# fuseV0_1.net
KiCad netlist of a schematic drawn in Altium Designer
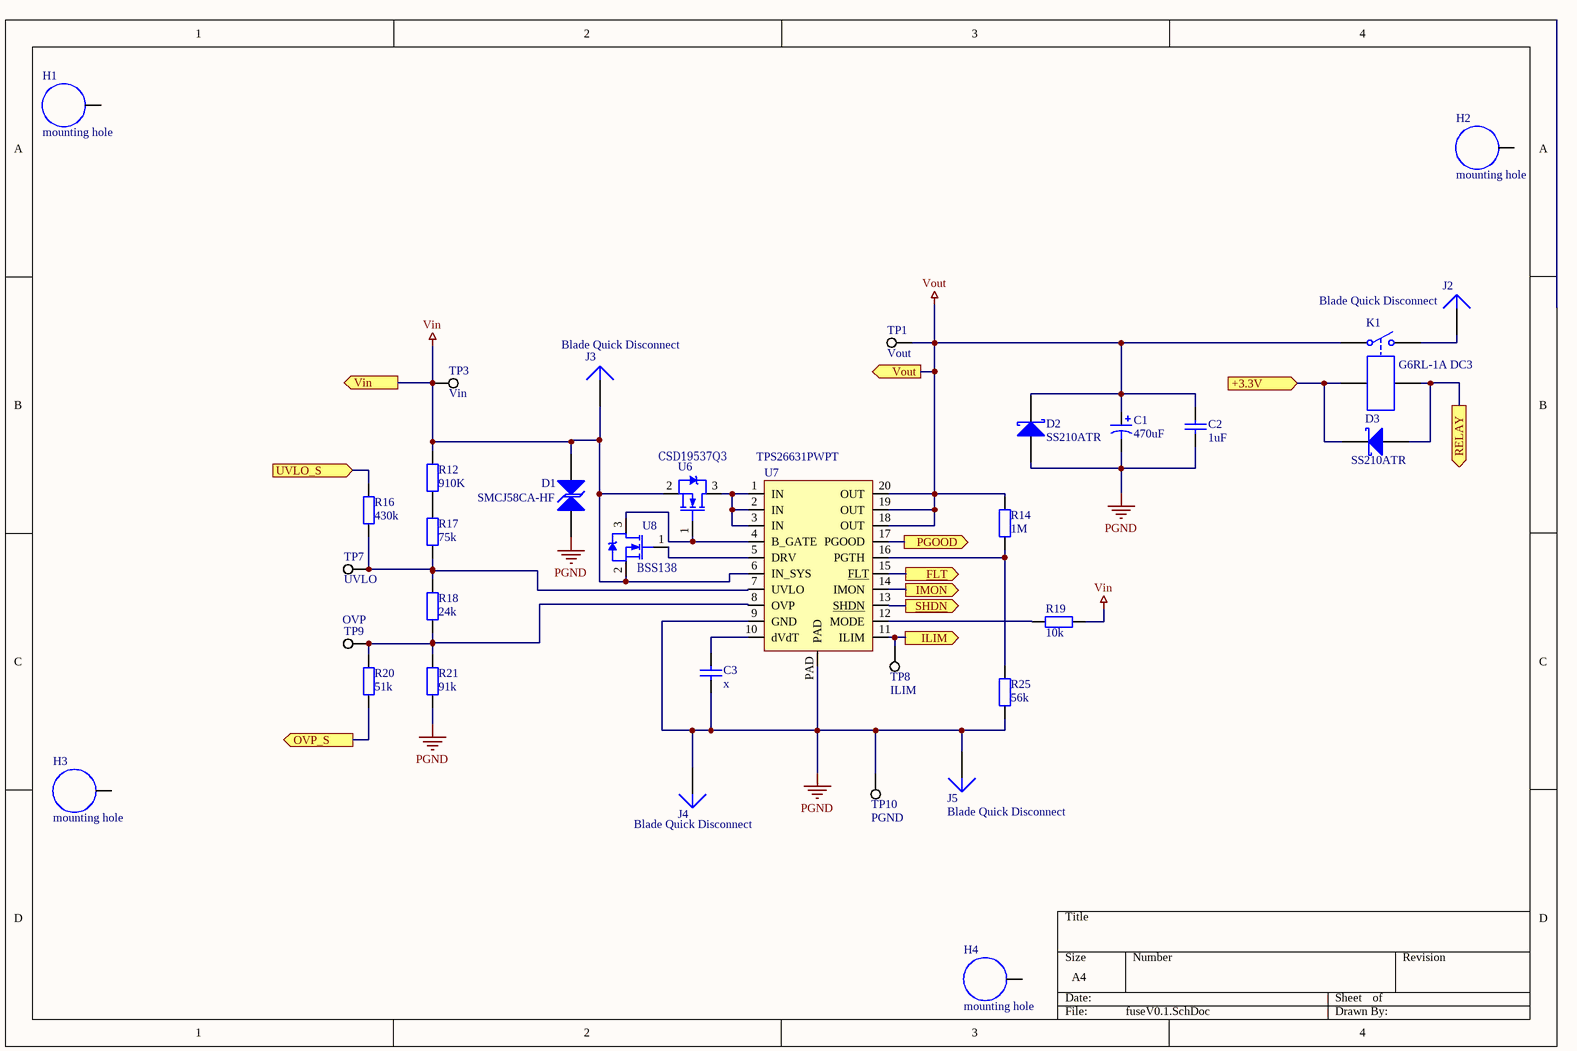
[diagram p0: fuseV0.1.SchDoc]

(export (version "E")
  (design (tool "Eeschema 10.0.6"))
  (components
    (comp (ref "C1")
      (value "470uF")
      (footprint "CAP_16MM_SMD")
      (libsource (lib "generic_components") (part "cap pol"))
    )
    (comp (ref "C2") (value "1uF") (footprint "0805") (libsource (lib "generic_components") (part "cap")))
    (comp (ref "C3") (value "x") (footprint "0805") (libsource (lib "generic_components") (part "cap")))
    (comp (ref "D1")
      (value "SMCJ58CA-HF")
      (footprint "DO-214AB-SMC Bipolar")
      (libsource (lib "generic_components") (part "TVS Diode"))
    )
    (comp (ref "D2")
      (value "SS210ATR")
      (footprint "DO-214AC, SMA")
      (libsource (lib "generic_components") (part "shotkey diode"))
    )
    (comp (ref "D3")
      (value "SS210ATR")
      (footprint "DO-214AC, SMA")
      (libsource (lib "generic_components") (part "shotkey diode"))
    )
    (comp (ref "H1")
      (value "mounting hole")
      (footprint "M3 HOLE iso")
      (libsource (lib "generic_components") (part "mounting hole"))
    )
    (comp (ref "H2")
      (value "mounting hole")
      (footprint "M3 HOLE iso")
      (libsource (lib "generic_components") (part "mounting hole"))
    )
    (comp (ref "H3")
      (value "mounting hole")
      (footprint "M3 HOLE iso")
      (libsource (lib "generic_components") (part "mounting hole"))
    )
    (comp (ref "H4")
      (value "mounting hole")
      (footprint "M3 HOLE iso")
      (libsource (lib "generic_components") (part "mounting hole"))
    )
    (comp (ref "J2")
      (value "Blade Quick Disconnect")
      (footprint "TE blade connector")
      (libsource (lib "generic_conn") (part "Blade Quick Disconnect"))
    )
    (comp (ref "J3")
      (value "Blade Quick Disconnect")
      (footprint "TE blade connector")
      (libsource (lib "generic_conn") (part "Blade Quick Disconnect"))
    )
    (comp (ref "J4")
      (value "Blade Quick Disconnect")
      (footprint "TE blade connector")
      (libsource (lib "generic_conn") (part "Blade Quick Disconnect"))
    )
    (comp (ref "J5")
      (value "Blade Quick Disconnect")
      (footprint "TE blade connector")
      (libsource (lib "generic_conn") (part "Blade Quick Disconnect"))
    )
    (comp (ref "K1")
      (value "G6RL-1A DC3")
      (footprint "G6RL-1A DC3 relay")
      (libsource (lib "generic_components") (part "Relay"))
    )
    (comp (ref "R12")
      (value "910K")
      (footprint "0805")
      (libsource (lib "generic_components") (part "res0805"))
    )
    (comp (ref "R14") (value "1M") (footprint "0805") (libsource (lib "generic_components") (part "res0805")))
    (comp (ref "R16")
      (value "430k")
      (footprint "0805")
      (libsource (lib "generic_components") (part "res0805"))
    )
    (comp (ref "R17")
      (value "75k")
      (footprint "0805")
      (libsource (lib "generic_components") (part "res0805"))
    )
    (comp (ref "R18")
      (value "24k")
      (footprint "0805")
      (libsource (lib "generic_components") (part "res0805"))
    )
    (comp (ref "R19") (value "10k") (footprint "0805") (libsource (lib "") (part "res0805_1")))
    (comp (ref "R20")
      (value "51k")
      (footprint "0805")
      (libsource (lib "generic_components") (part "res0805"))
    )
    (comp (ref "R21")
      (value "91k")
      (footprint "0805")
      (libsource (lib "generic_components") (part "res0805"))
    )
    (comp (ref "R25")
      (value "56k")
      (footprint "0805")
      (libsource (lib "generic_components") (part "res0805"))
    )
    (comp (ref "TP1")
      (value "Vout")
      (footprint "Test Loop 1.6mm")
      (libsource (lib "generic_components") (part "Test point"))
    )
    (comp (ref "TP3")
      (value "Vin")
      (footprint "Test Loop 1.6mm")
      (libsource (lib "generic_components") (part "Test point"))
    )
    (comp (ref "TP7")
      (value "UVLO")
      (footprint "Test Loop 1.6mm")
      (libsource (lib "generic_components") (part "Test point"))
    )
    (comp (ref "TP8")
      (value "ILIM")
      (footprint "Test Loop 1.6mm")
      (libsource (lib "generic_components") (part "Test point"))
    )
    (comp (ref "TP9")
      (value "OVP")
      (footprint "Test Loop 1.6mm")
      (libsource (lib "generic_components") (part "Test point"))
    )
    (comp (ref "TP10")
      (value "PGND")
      (footprint "Test Loop 1.6mm")
      (libsource (lib "generic_components") (part "Test point"))
    )
    (comp (ref "U6")
      (value "‎CSD19537Q3‎")
      (footprint "8-VSON (3,3x3,3)")
      (libsource (lib "generic_components") (part "N-mosfet en"))
    )
    (comp (ref "U7")
      (value "TPS26631PWPT")
      (footprint "TSSOP_P065S6.6x6.6")
      (libsource (lib "ti") (part "TPS26631PWPT"))
    )
    (comp (ref "U8")
      (value "BSS138‎")
      (footprint "SOT-23-3")
      (libsource (lib "generic_components") (part "N-mosfet en"))
    )
  )
  (nets
    (net (code "1") (name "/+3.3V") (class "Default")
      (node (ref "D3") (pin "2") (pinfunction "K_2") (pintype "passive"))
      (node (ref "K1") (pin "1") (pinfunction "1_1") (pintype "passive"))
    )
    (net (code "2") (name "/FLT") (class "Default")
      (node (ref "U7") (pin "15") (pinfunction "FLT_15") (pintype "passive"))
    )
    (net (code "3") (name "/ILIM") (class "Default")
      (node (ref "TP8") (pin "1") (pintype "passive"))
      (node (ref "U7") (pin "11") (pinfunction "ILIM_11") (pintype "passive"))
    )
    (net (code "4") (name "/IMON") (class "Default")
      (node (ref "U7") (pin "14") (pinfunction "IMON_14") (pintype "passive"))
    )
    (net (code "5") (name "/OVP_S") (class "Default") (node (ref "R20") (pin "1") (pintype "passive")))
    (net (code "6") (name "/PGOOD") (class "Default")
      (node (ref "U7") (pin "17") (pinfunction "PGOOD_17") (pintype "passive"))
    )
    (net (code "7") (name "/RELAY") (class "Default")
      (node (ref "D3") (pin "1") (pinfunction "A_1") (pintype "passive"))
      (node (ref "K1") (pin "5") (pinfunction "5_5") (pintype "passive"))
    )
    (net (code "8") (name "/SHDN") (class "Default")
      (node (ref "U7") (pin "13") (pinfunction "SHDN_13") (pintype "passive"))
    )
    (net (code "9") (name "/UVLO_S") (class "Default")
      (node (ref "R16") (pin "2") (pinfunction "2_2") (pintype "passive"))
    )
    (net (code "10") (name "Net-(J2-Pad1)") (class "Default")
      (node (ref "J2") (pin "1") (pinfunction "1_1") (pintype "passive"))
      (node (ref "K1") (pin "3") (pinfunction "3_3") (pintype "passive"))
    )
    (net (code "11") (name "Net-(R12-Pad1)") (class "Default")
      (node (ref "R12") (pin "1") (pintype "passive"))
      (node (ref "R17") (pin "2") (pinfunction "2_2") (pintype "passive"))
    )
    (net (code "12") (name "Net-(U6-G)") (class "Default")
      (node (ref "U6") (pin "1") (pinfunction "G_1") (pintype "passive"))
      (node (ref "U7") (pin "4") (pinfunction "B_GATE_4") (pintype "passive"))
      (node (ref "U8") (pin "3") (pinfunction "S_3") (pintype "passive"))
    )
    (net (code "13") (name "Net-(U6-S)") (class "Default")
      (node (ref "U6") (pin "3") (pinfunction "S_3") (pintype "passive"))
      (node (ref "U7") (pin "1") (pinfunction "IN_1") (pintype "passive"))
      (node (ref "U7") (pin "2") (pinfunction "IN_2") (pintype "passive"))
      (node (ref "U7") (pin "3") (pinfunction "IN_3") (pintype "passive"))
    )
    (net (code "14") (name "Net-(U7-DRV)") (class "Default")
      (node (ref "U7") (pin "5") (pinfunction "DRV_5") (pintype "passive"))
      (node (ref "U8") (pin "1") (pinfunction "G_1") (pintype "passive"))
    )
    (net (code "15") (name "Net-(U7-MODE)") (class "Default")
      (node (ref "R19") (pin "2") (pinfunction "2_2") (pintype "passive"))
      (node (ref "U7") (pin "12") (pinfunction "MODE_12") (pintype "passive"))
    )
    (net (code "16") (name "Net-(U7-OVP)") (class "Default")
      (node (ref "R18") (pin "1") (pintype "passive"))
      (node (ref "R20") (pin "2") (pinfunction "2_2") (pintype "passive"))
      (node (ref "R21") (pin "2") (pinfunction "2_2") (pintype "passive"))
      (node (ref "TP9") (pin "1") (pintype "passive"))
      (node (ref "U7") (pin "8") (pinfunction "OVP_8") (pintype "passive"))
    )
    (net (code "17") (name "Net-(U7-PGTH)") (class "Default")
      (node (ref "R14") (pin "1") (pintype "passive"))
      (node (ref "R25") (pin "2") (pinfunction "2_2") (pintype "passive"))
      (node (ref "U7") (pin "16") (pinfunction "PGTH_16") (pintype "passive"))
    )
    (net (code "18") (name "Net-(U7-UVLO)") (class "Default")
      (node (ref "R16") (pin "1") (pintype "passive"))
      (node (ref "R17") (pin "1") (pintype "passive"))
      (node (ref "R18") (pin "2") (pinfunction "2_2") (pintype "passive"))
      (node (ref "TP7") (pin "1") (pintype "passive"))
      (node (ref "U7") (pin "7") (pinfunction "UVLO_7") (pintype "passive"))
    )
    (net (code "19") (name "Net-(U7-dVdT)") (class "Default")
      (node (ref "C3") (pin "1") (pinfunction "1_1") (pintype "passive"))
      (node (ref "U7") (pin "10") (pinfunction "dVdT_10") (pintype "passive"))
    )
    (net (code "20") (name "PGND") (class "Default")
      (node (ref "C1") (pin "2") (pinfunction "2_2") (pintype "passive"))
      (node (ref "C2") (pin "1") (pinfunction "1_1") (pintype "passive"))
      (node (ref "C3") (pin "2") (pinfunction "2_2") (pintype "passive"))
      (node (ref "D1") (pin "1") (pinfunction "A_1") (pintype "passive"))
      (node (ref "D2") (pin "1") (pinfunction "A_1") (pintype "passive"))
      (node (ref "J4") (pin "1") (pinfunction "1_1") (pintype "passive"))
      (node (ref "J5") (pin "1") (pinfunction "1_1") (pintype "passive"))
      (node (ref "R21") (pin "1") (pintype "passive"))
      (node (ref "R25") (pin "1") (pintype "passive"))
      (node (ref "TP10") (pin "1") (pintype "passive"))
      (node (ref "U7") (pin "9") (pinfunction "GND_9") (pintype "passive"))
      (node (ref "U7") (pin "PAD") (pinfunction "PAD_PAD") (pintype "passive"))
    )
    (net (code "21") (name "Vin") (class "Default")
      (node (ref "D1") (pin "2") (pinfunction "K_2") (pintype "passive"))
      (node (ref "J3") (pin "1") (pinfunction "1_1") (pintype "passive"))
      (node (ref "R12") (pin "2") (pinfunction "2_2") (pintype "passive"))
      (node (ref "R19") (pin "1") (pintype "passive"))
      (node (ref "TP3") (pin "1") (pintype "passive"))
      (node (ref "U6") (pin "2") (pinfunction "D_2") (pintype "passive"))
      (node (ref "U7") (pin "6") (pinfunction "IN_SYS_6") (pintype "passive"))
      (node (ref "U8") (pin "2") (pinfunction "D_2") (pintype "passive"))
    )
    (net (code "22") (name "Vout") (class "Default")
      (node (ref "C1") (pin "1") (pinfunction "1_1") (pintype "passive"))
      (node (ref "C2") (pin "2") (pinfunction "2_2") (pintype "passive"))
      (node (ref "D2") (pin "2") (pinfunction "K_2") (pintype "passive"))
      (node (ref "K1") (pin "2") (pinfunction "2_2") (pintype "passive"))
      (node (ref "R14") (pin "2") (pinfunction "2_2") (pintype "passive"))
      (node (ref "TP1") (pin "1") (pintype "passive"))
      (node (ref "U7") (pin "18") (pinfunction "OUT_18") (pintype "passive"))
      (node (ref "U7") (pin "19") (pinfunction "OUT_19") (pintype "passive"))
      (node (ref "U7") (pin "20") (pinfunction "OUT_20") (pintype "passive"))
    )
    (net (code "23") (name "unconnected-(H1-Pad1)") (class "Default")
      (node (ref "H1") (pin "1") (pintype "passive"))
    )
    (net (code "24") (name "unconnected-(H2-Pad1)") (class "Default")
      (node (ref "H2") (pin "1") (pintype "passive"))
    )
    (net (code "25") (name "unconnected-(H3-Pad1)") (class "Default")
      (node (ref "H3") (pin "1") (pintype "passive"))
    )
    (net (code "26") (name "unconnected-(H4-Pad1)") (class "Default")
      (node (ref "H4") (pin "1") (pintype "passive"))
    )
  )
)
